# v11.net
KiCad netlist of a schematic drawn in EAGLE
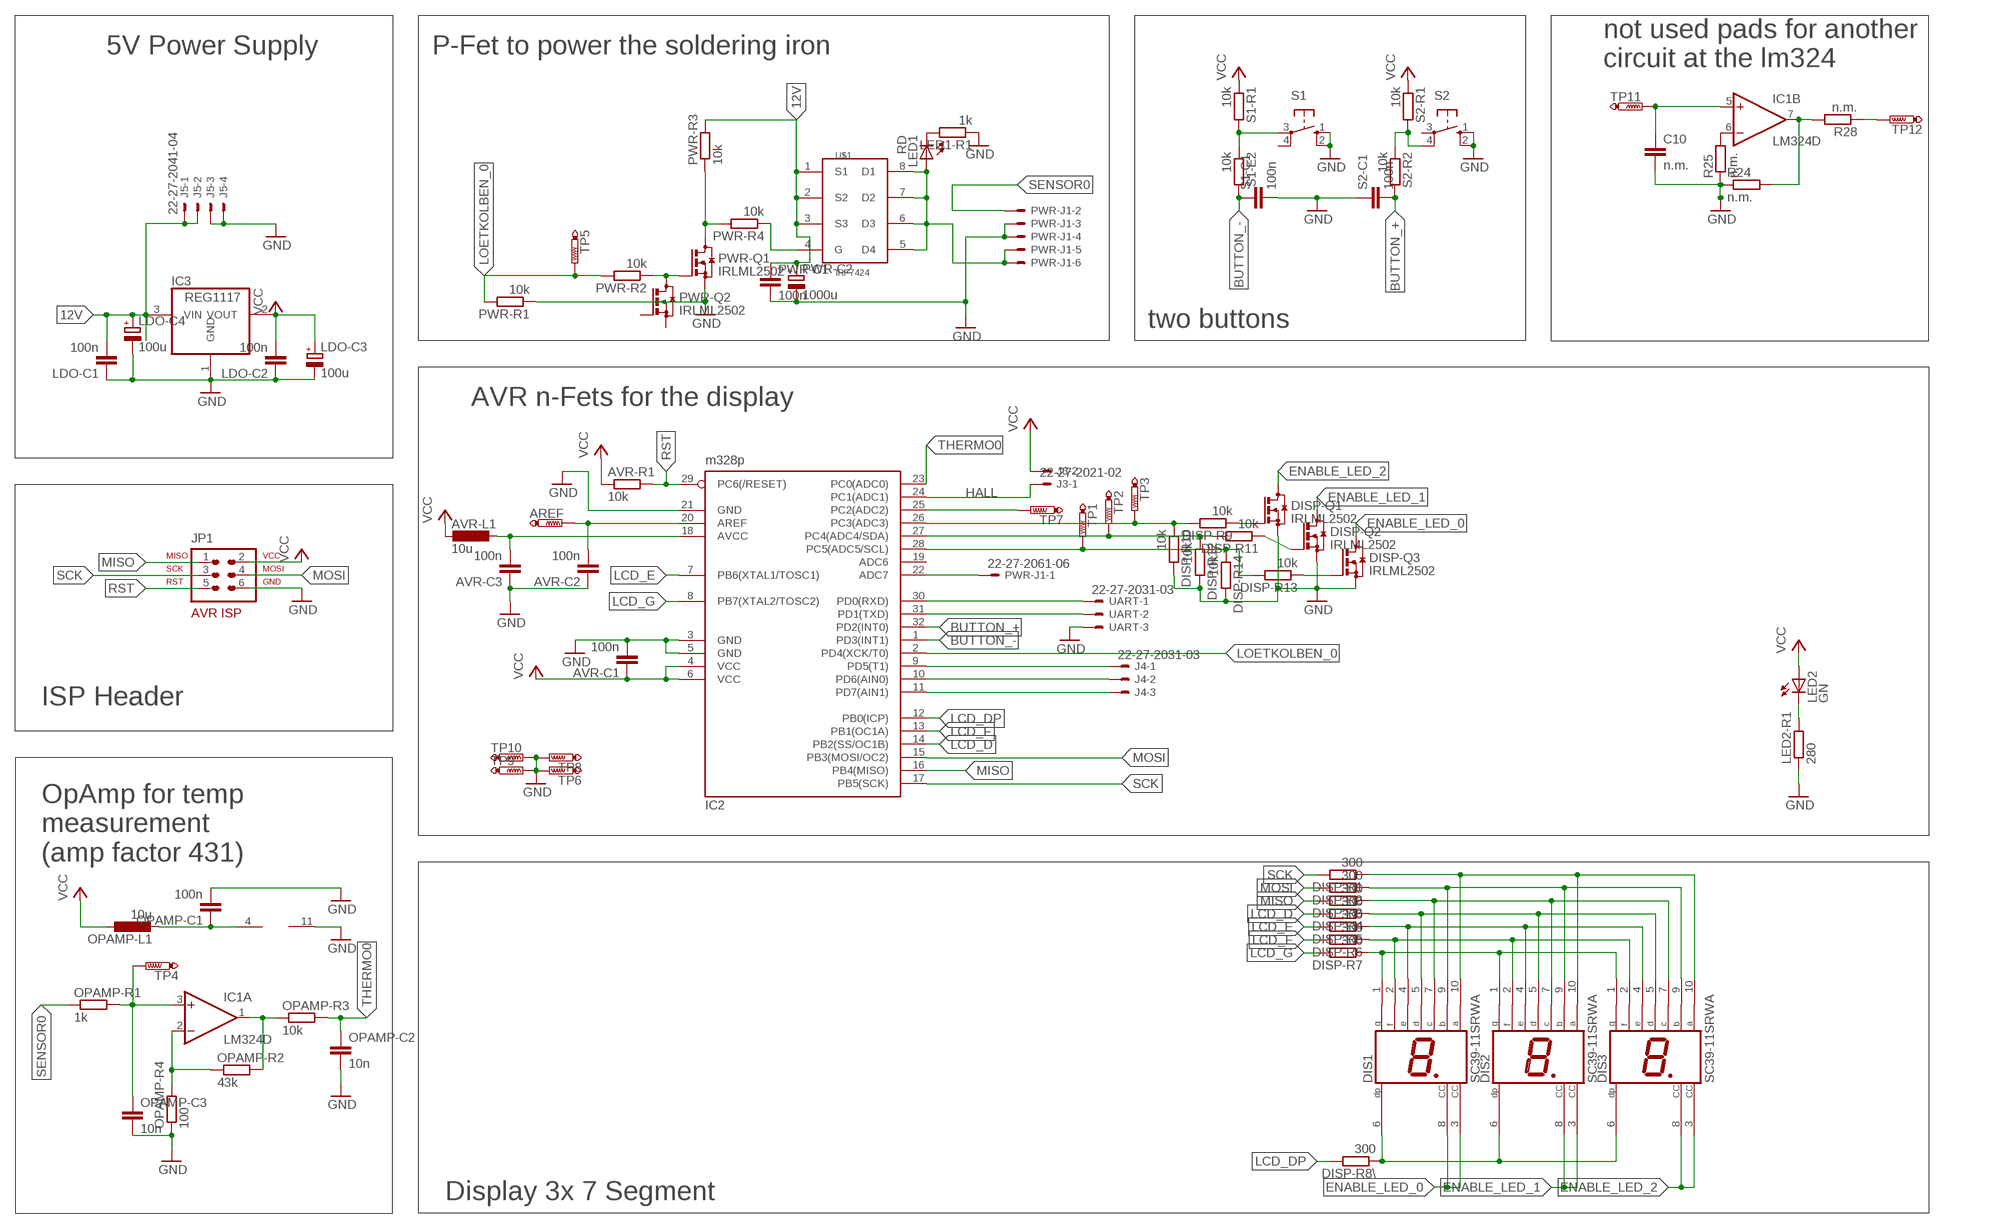
[diagram p0: schematic, sheet 1]

(export (version "E")
  (design (tool "Eeschema 10.0.6"))
  (components
    (comp (ref "AREF")
      (value "PTR1B1,27")
      (footprint "eagle-import:B1,27")
      (libsource (lib "eagle-import") (part "PTR1B1,27"))
    )
    (comp (ref "AVR-C1")
      (value "100n")
      (footprint "eagle-import:C0603")
      (libsource (lib "eagle-import") (part "C-EUC0603"))
    )
    (comp (ref "AVR-C2")
      (value "100n")
      (footprint "eagle-import:C0603")
      (libsource (lib "eagle-import") (part "C-EUC0603"))
    )
    (comp (ref "AVR-C3")
      (value "100n")
      (footprint "eagle-import:C0603")
      (libsource (lib "eagle-import") (part "C-EUC0603"))
    )
    (comp (ref "AVR-L1")
      (value "10u")
      (footprint "eagle-import:L2825P")
      (libsource (lib "eagle-import") (part "L-EUL2825P"))
    )
    (comp (ref "AVR-R1")
      (value "10k")
      (footprint "eagle-import:R0603")
      (libsource (lib "eagle-import") (part "R-EU_R0603"))
    )
    (comp (ref "C10")
      (value "n.m.")
      (footprint "eagle-import:C0603")
      (libsource (lib "eagle-import") (part "C-EUC0603"))
    )
    (comp (ref "DIS1")
      (value "SC39-11SRWA")
      (footprint "eagle-import:HDSP-E")
      (libsource (lib "eagle-import") (part "SC39-11SRWA"))
    )
    (comp (ref "DIS2")
      (value "SC39-11SRWA")
      (footprint "eagle-import:HDSP-E")
      (libsource (lib "eagle-import") (part "SC39-11SRWA"))
    )
    (comp (ref "DIS3")
      (value "SC39-11SRWA")
      (footprint "eagle-import:HDSP-E")
      (libsource (lib "eagle-import") (part "SC39-11SRWA"))
    )
    (comp (ref "DISP-Q1")
      (value "IRLML2502")
      (footprint "eagle-import:SOT23")
      (libsource (lib "eagle-import") (part "BSS123"))
    )
    (comp (ref "DISP-Q2")
      (value "IRLML2502")
      (footprint "eagle-import:SOT23")
      (libsource (lib "eagle-import") (part "BSS123"))
    )
    (comp (ref "DISP-Q3")
      (value "IRLML2502")
      (footprint "eagle-import:SOT23")
      (libsource (lib "eagle-import") (part "BSS123"))
    )
    (comp (ref "DISP-R1")
      (value "300")
      (footprint "eagle-import:R0603")
      (libsource (lib "eagle-import") (part "R-EU_R0603"))
    )
    (comp (ref "DISP-R2")
      (value "300")
      (footprint "eagle-import:R0603")
      (libsource (lib "eagle-import") (part "R-EU_R0603"))
    )
    (comp (ref "DISP-R3")
      (value "300")
      (footprint "eagle-import:R0603")
      (libsource (lib "eagle-import") (part "R-EU_R0603"))
    )
    (comp (ref "DISP-R4")
      (value "300")
      (footprint "eagle-import:R0603")
      (libsource (lib "eagle-import") (part "R-EU_R0603"))
    )
    (comp (ref "DISP-R5")
      (value "300")
      (footprint "eagle-import:R0603")
      (libsource (lib "eagle-import") (part "R-EU_R0603"))
    )
    (comp (ref "DISP-R6")
      (value "300")
      (footprint "eagle-import:R0603")
      (libsource (lib "eagle-import") (part "R-EU_R0603"))
    )
    (comp (ref "DISP-R7")
      (value "300")
      (footprint "eagle-import:R0603")
      (libsource (lib "eagle-import") (part "R-EU_R0603"))
    )
    (comp (ref "DISP-R8\\")
      (value "300")
      (footprint "eagle-import:R0603")
      (libsource (lib "eagle-import") (part "R-EU_R0603"))
    )
    (comp (ref "DISP-R9")
      (value "10k")
      (footprint "eagle-import:R0603")
      (libsource (lib "eagle-import") (part "R-EU_R0603"))
    )
    (comp (ref "DISP-R10")
      (value "10k")
      (footprint "eagle-import:R0603")
      (libsource (lib "eagle-import") (part "R-EU_R0603"))
    )
    (comp (ref "DISP-R11")
      (value "10k")
      (footprint "eagle-import:R0603")
      (libsource (lib "eagle-import") (part "R-EU_R0603"))
    )
    (comp (ref "DISP-R12")
      (value "10k")
      (footprint "eagle-import:R0603")
      (libsource (lib "eagle-import") (part "R-EU_R0603"))
    )
    (comp (ref "DISP-R13")
      (value "10k")
      (footprint "eagle-import:R0603")
      (libsource (lib "eagle-import") (part "R-EU_R0603"))
    )
    (comp (ref "DISP-R14")
      (value "10k")
      (footprint "eagle-import:R0603")
      (libsource (lib "eagle-import") (part "R-EU_R0603"))
    )
    (comp (ref "IC1")
      (value "LM324D")
      (footprint "eagle-import:SO14")
      (libsource (lib "eagle-import") (part "LM324D"))
    )
    (comp (ref "IC2")
      (value "m328p")
      (footprint "eagle-import:TQFP32-08")
      (fields (field (name "MPN") "ATMEGA8-16AU"))
      (libsource (lib "eagle-import") (part "MEGA8-AI"))
    )
    (comp (ref "IC3")
      (value "REG1117")
      (footprint "eagle-import:SOT223")
      (libsource (lib "eagle-import") (part "REG1117"))
    )
    (comp (ref "J3")
      (value "22-27-2021-02")
      (footprint "eagle-import:6410-02")
      (libsource (lib "eagle-import") (part "22-?-0227-2021"))
    )
    (comp (ref "J4")
      (value "22-27-2031-03")
      (footprint "eagle-import:6410-03")
      (libsource (lib "eagle-import") (part "22-?-0327-2031"))
    )
    (comp (ref "J5")
      (value "22-27-2041-04")
      (footprint "eagle-import:6410-04")
      (libsource (lib "eagle-import") (part "22-?-0427-2041"))
    )
    (comp (ref "JP1")
      (value "AVR-ISP-6VERT")
      (footprint "eagle-import:AVR-ISP-6")
      (libsource (lib "eagle-import") (part "AVR-ISP-6VERT"))
    )
    (comp (ref "LDO-C1")
      (value "100n")
      (footprint "eagle-import:C0603")
      (libsource (lib "eagle-import") (part "C-EUC0603"))
    )
    (comp (ref "LDO-C2")
      (value "100n")
      (footprint "eagle-import:C0603")
      (libsource (lib "eagle-import") (part "C-EUC0603"))
    )
    (comp (ref "LDO-C3")
      (value "100u")
      (footprint "eagle-import:E2-5")
      (libsource (lib "eagle-import") (part "CPOL-EUE2-5"))
    )
    (comp (ref "LDO-C4")
      (value "100u")
      (footprint "eagle-import:E2-5")
      (libsource (lib "eagle-import") (part "CPOL-EUE2-5"))
    )
    (comp (ref "LED1")
      (value "RD")
      (footprint "eagle-import:CHIP-LED0805")
      (libsource (lib "eagle-import") (part "LEDCHIP-LED0805"))
    )
    (comp (ref "LED1-R1")
      (value "1k")
      (footprint "eagle-import:R0603")
      (libsource (lib "eagle-import") (part "R-EU_R0603"))
    )
    (comp (ref "LED2")
      (value "GN")
      (footprint "eagle-import:CHIP-LED0805")
      (libsource (lib "eagle-import") (part "LEDCHIP-LED0805"))
    )
    (comp (ref "LED2-R1")
      (value "280")
      (footprint "eagle-import:R0603")
      (libsource (lib "eagle-import") (part "R-EU_R0603"))
    )
    (comp (ref "OPAMP-C1")
      (value "100n")
      (footprint "eagle-import:C0603")
      (libsource (lib "eagle-import") (part "C-EUC0603"))
    )
    (comp (ref "OPAMP-C2")
      (value "10n")
      (footprint "eagle-import:C0603")
      (libsource (lib "eagle-import") (part "C-EUC0603"))
    )
    (comp (ref "OPAMP-C3")
      (value "10n")
      (footprint "eagle-import:C0603")
      (libsource (lib "eagle-import") (part "C-EUC0603"))
    )
    (comp (ref "OPAMP-L1")
      (value "10u")
      (footprint "eagle-import:L2825P")
      (libsource (lib "eagle-import") (part "L-EUL2825P"))
    )
    (comp (ref "OPAMP-R1")
      (value "1k")
      (footprint "eagle-import:R0603")
      (libsource (lib "eagle-import") (part "R-EU_R0603"))
    )
    (comp (ref "OPAMP-R2")
      (value "43k")
      (footprint "eagle-import:R0603")
      (libsource (lib "eagle-import") (part "R-EU_R0603"))
    )
    (comp (ref "OPAMP-R3")
      (value "10k")
      (footprint "eagle-import:R0603")
      (libsource (lib "eagle-import") (part "R-EU_R0603"))
    )
    (comp (ref "OPAMP-R4")
      (value "100")
      (footprint "eagle-import:R0603")
      (libsource (lib "eagle-import") (part "R-EU_R0603"))
    )
    (comp (ref "PWR-C1")
      (value "100n")
      (footprint "eagle-import:C0603")
      (libsource (lib "eagle-import") (part "C-EUC0603"))
    )
    (comp (ref "PWR-C2")
      (value "1000u")
      (footprint "eagle-import:E5-13")
      (libsource (lib "eagle-import") (part "CPOL-EUE5-13"))
    )
    (comp (ref "PWR-J1")
      (value "22-27-2061-06")
      (footprint "eagle-import:6410-06")
      (libsource (lib "eagle-import") (part "22-?-0627-2061"))
    )
    (comp (ref "PWR-Q1")
      (value "IRLML2502")
      (footprint "eagle-import:SOT23")
      (libsource (lib "eagle-import") (part "BSS123"))
    )
    (comp (ref "PWR-Q2")
      (value "IRLML2502")
      (footprint "eagle-import:SOT23")
      (libsource (lib "eagle-import") (part "BSS123"))
    )
    (comp (ref "PWR-R1")
      (value "10k")
      (footprint "eagle-import:R0603")
      (libsource (lib "eagle-import") (part "R-EU_R0603"))
    )
    (comp (ref "PWR-R2")
      (value "10k")
      (footprint "eagle-import:R0603")
      (libsource (lib "eagle-import") (part "R-EU_R0603"))
    )
    (comp (ref "PWR-R3")
      (value "10k")
      (footprint "eagle-import:R0603")
      (libsource (lib "eagle-import") (part "R-EU_R0603"))
    )
    (comp (ref "PWR-R4")
      (value "10k")
      (footprint "eagle-import:R0603")
      (libsource (lib "eagle-import") (part "R-EU_R0603"))
    )
    (comp (ref "R24")
      (value "n.m.")
      (footprint "eagle-import:R0603")
      (libsource (lib "eagle-import") (part "R-EU_R0603"))
    )
    (comp (ref "R25")
      (value "n.m.")
      (footprint "eagle-import:R0603")
      (libsource (lib "eagle-import") (part "R-EU_R0603"))
    )
    (comp (ref "R28")
      (value "n.m.")
      (footprint "eagle-import:R0603")
      (libsource (lib "eagle-import") (part "R-EU_R0603"))
    )
    (comp (ref "S1")
      (value "10-XX")
      (footprint "eagle-import:B3F-10XX")
      (fields (field (name "MPN") "B3F-1000"))
      (libsource (lib "eagle-import") (part "10-XX"))
    )
    (comp (ref "S1-C1")
      (value "100n")
      (footprint "eagle-import:C0603")
      (libsource (lib "eagle-import") (part "C-EUC0603"))
    )
    (comp (ref "S1-E2")
      (value "10k")
      (footprint "eagle-import:R0603")
      (libsource (lib "eagle-import") (part "R-EU_R0603"))
    )
    (comp (ref "S1-R1")
      (value "10k")
      (footprint "eagle-import:R0603")
      (libsource (lib "eagle-import") (part "R-EU_R0603"))
    )
    (comp (ref "S2")
      (value "10-XX")
      (footprint "eagle-import:B3F-10XX")
      (fields (field (name "MPN") "B3F-1000"))
      (libsource (lib "eagle-import") (part "10-XX"))
    )
    (comp (ref "S2-C1")
      (value "100n")
      (footprint "eagle-import:C0603")
      (libsource (lib "eagle-import") (part "C-EUC0603"))
    )
    (comp (ref "S2-R1")
      (value "10k")
      (footprint "eagle-import:R0603")
      (libsource (lib "eagle-import") (part "R-EU_R0603"))
    )
    (comp (ref "S2-R2")
      (value "10k")
      (footprint "eagle-import:R0603")
      (libsource (lib "eagle-import") (part "R-EU_R0603"))
    )
    (comp (ref "TP1")
      (value "PTR1B1,27")
      (footprint "eagle-import:B1,27")
      (libsource (lib "eagle-import") (part "PTR1B1,27"))
    )
    (comp (ref "TP2")
      (value "PTR1B1,27")
      (footprint "eagle-import:B1,27")
      (libsource (lib "eagle-import") (part "PTR1B1,27"))
    )
    (comp (ref "TP3")
      (value "PTR1B1,27")
      (footprint "eagle-import:B1,27")
      (libsource (lib "eagle-import") (part "PTR1B1,27"))
    )
    (comp (ref "TP4")
      (value "PTR1B1,27")
      (footprint "eagle-import:B1,27")
      (libsource (lib "eagle-import") (part "PTR1B1,27"))
    )
    (comp (ref "TP5")
      (value "PTR1B1,27")
      (footprint "eagle-import:B1,27")
      (libsource (lib "eagle-import") (part "PTR1B1,27"))
    )
    (comp (ref "TP6")
      (value "PTR1B1,27")
      (footprint "eagle-import:B1,27")
      (libsource (lib "eagle-import") (part "PTR1B1,27"))
    )
    (comp (ref "TP7")
      (value "PTR1B1,27")
      (footprint "eagle-import:B1,27")
      (libsource (lib "eagle-import") (part "PTR1B1,27"))
    )
    (comp (ref "TP8")
      (value "PTR1B1,27")
      (footprint "eagle-import:B1,27")
      (libsource (lib "eagle-import") (part "PTR1B1,27"))
    )
    (comp (ref "TP9")
      (value "PTR1B1,27")
      (footprint "eagle-import:B1,27")
      (libsource (lib "eagle-import") (part "PTR1B1,27"))
    )
    (comp (ref "TP10")
      (value "PTR1B1,27")
      (footprint "eagle-import:B1,27")
      (libsource (lib "eagle-import") (part "PTR1B1,27"))
    )
    (comp (ref "TP11")
      (value "PTR1B1,27")
      (footprint "eagle-import:B1,27")
      (libsource (lib "eagle-import") (part "PTR1B1,27"))
    )
    (comp (ref "TP12")
      (value "PTR1B1,27")
      (footprint "eagle-import:B1,27")
      (libsource (lib "eagle-import") (part "PTR1B1,27"))
    )
    (comp (ref "U$1")
      (value "IRF7424")
      (footprint "eagle-import:SO-08")
      (libsource (lib "eagle-import") (part "IRF7424"))
    )
    (comp (ref "UART")
      (value "22-27-2031-03")
      (footprint "eagle-import:6410-03")
      (libsource (lib "eagle-import") (part "22-?-0327-2031"))
    )
  )
  (nets
    (net (code "1") (name "/HALL") (class "Default")
      (node (ref "IC2") (pin "24") (pinfunction "PC1(ADC1)_24") (pintype "bidirectional"))
      (node (ref "J3") (pin "1") (pinfunction "S_1") (pintype "passive"))
    )
    (net (code "2") (name "12V") (class "Default")
      (node (ref "IC3") (pin "3") (pinfunction "VIN_3") (pintype "input"))
      (node (ref "J5") (pin "1") (pinfunction "S_1") (pintype "passive"))
      (node (ref "J5") (pin "2") (pinfunction "S_2") (pintype "passive"))
      (node (ref "LDO-C1") (pin "2") (pinfunction "2_2") (pintype "passive"))
      (node (ref "LDO-C4") (pin "+") (pinfunction "+_+") (pintype "passive"))
      (node (ref "PWR-C1") (pin "1") (pinfunction "1_1") (pintype "passive"))
      (node (ref "PWR-C2") (pin "+") (pinfunction "+_+") (pintype "passive"))
      (node (ref "PWR-R3") (pin "2") (pinfunction "2_2") (pintype "passive"))
      (node (ref "U$1") (pin "1") (pinfunction "S1_1") (pintype "bidirectional"))
      (node (ref "U$1") (pin "2") (pinfunction "S2_2") (pintype "bidirectional"))
      (node (ref "U$1") (pin "3") (pinfunction "S3_3") (pintype "bidirectional"))
    )
    (net (code "3") (name "BUTTON_+") (class "Default")
      (node (ref "IC2") (pin "32") (pinfunction "PD2(INT0)_32") (pintype "bidirectional"))
      (node (ref "S2-C1") (pin "2") (pinfunction "2_2") (pintype "passive"))
      (node (ref "S2-R2") (pin "2") (pinfunction "2_2") (pintype "passive"))
    )
    (net (code "4") (name "BUTTON_-") (class "Default")
      (node (ref "IC2") (pin "1") (pinfunction "PD3(INT1)_1") (pintype "bidirectional"))
      (node (ref "S1-C1") (pin "1") (pinfunction "1_1") (pintype "passive"))
      (node (ref "S1-E2") (pin "2") (pinfunction "2_2") (pintype "passive"))
    )
    (net (code "5") (name "ENABLE_LED_0") (class "Default")
      (node (ref "DIS1") (pin "3") (pinfunction "CC_3") (pintype "passive"))
      (node (ref "DIS1") (pin "8") (pinfunction "CC_8") (pintype "passive"))
      (node (ref "DISP-Q3") (pin "3") (pinfunction "D_3") (pintype "passive"))
    )
    (net (code "6") (name "ENABLE_LED_1") (class "Default")
      (node (ref "DIS2") (pin "3") (pinfunction "CC_3") (pintype "passive"))
      (node (ref "DIS2") (pin "8") (pinfunction "CC_8") (pintype "passive"))
      (node (ref "DISP-Q2") (pin "3") (pinfunction "D_3") (pintype "passive"))
    )
    (net (code "7") (name "ENABLE_LED_2") (class "Default")
      (node (ref "DIS3") (pin "3") (pinfunction "CC_3") (pintype "passive"))
      (node (ref "DIS3") (pin "8") (pinfunction "CC_8") (pintype "passive"))
      (node (ref "DISP-Q1") (pin "3") (pinfunction "D_3") (pintype "passive"))
    )
    (net (code "8") (name "GND") (class "Default")
      (node (ref "AVR-C1") (pin "2") (pinfunction "2_2") (pintype "passive"))
      (node (ref "AVR-C2") (pin "1") (pinfunction "1_1") (pintype "passive"))
      (node (ref "AVR-C3") (pin "1") (pinfunction "1_1") (pintype "passive"))
      (node (ref "C10") (pin "2") (pinfunction "2_2") (pintype "passive"))
      (node (ref "DISP-Q1") (pin "2") (pinfunction "S_2") (pintype "passive"))
      (node (ref "DISP-Q2") (pin "2") (pinfunction "S_2") (pintype "passive"))
      (node (ref "DISP-Q3") (pin "2") (pinfunction "S_2") (pintype "passive"))
      (node (ref "DISP-R10") (pin "2") (pinfunction "2_2") (pintype "passive"))
      (node (ref "DISP-R12") (pin "2") (pinfunction "2_2") (pintype "passive"))
      (node (ref "DISP-R14") (pin "2") (pinfunction "2_2") (pintype "passive"))
      (node (ref "IC1") (pin "11") (pinfunction "V-_11") (pintype "power_in"))
      (node (ref "IC2") (pin "21") (pinfunction "GND_21") (pintype "power_in"))
      (node (ref "IC2") (pin "3") (pinfunction "GND_3") (pintype "power_in"))
      (node (ref "IC2") (pin "5") (pinfunction "GND_5") (pintype "power_in"))
      (node (ref "IC3") (pin "1") (pinfunction "GND_1") (pintype "power_in"))
      (node (ref "J5") (pin "3") (pinfunction "S_3") (pintype "passive"))
      (node (ref "J5") (pin "4") (pinfunction "S_4") (pintype "passive"))
      (node (ref "JP1") (pin "6") (pinfunction "6_6") (pintype "passive"))
      (node (ref "LDO-C1") (pin "1") (pinfunction "1_1") (pintype "passive"))
      (node (ref "LDO-C2") (pin "1") (pinfunction "1_1") (pintype "passive"))
      (node (ref "LDO-C3") (pin "-") (pinfunction "-_-") (pintype "passive"))
      (node (ref "LDO-C4") (pin "-") (pinfunction "-_-") (pintype "passive"))
      (node (ref "LED1-R1") (pin "1") (pinfunction "1_1") (pintype "passive"))
      (node (ref "LED2-R1") (pin "1") (pinfunction "1_1") (pintype "passive"))
      (node (ref "OPAMP-C1") (pin "2") (pinfunction "2_2") (pintype "passive"))
      (node (ref "OPAMP-C2") (pin "2") (pinfunction "2_2") (pintype "passive"))
      (node (ref "OPAMP-C3") (pin "2") (pinfunction "2_2") (pintype "passive"))
      (node (ref "OPAMP-R4") (pin "1") (pinfunction "1_1") (pintype "passive"))
      (node (ref "PWR-C1") (pin "2") (pinfunction "2_2") (pintype "passive"))
      (node (ref "PWR-C2") (pin "-") (pinfunction "-_-") (pintype "passive"))
      (node (ref "PWR-J1") (pin "3") (pinfunction "S_3") (pintype "passive"))
      (node (ref "PWR-J1") (pin "4") (pinfunction "S_4") (pintype "passive"))
      (node (ref "PWR-Q1") (pin "2") (pinfunction "S_2") (pintype "passive"))
      (node (ref "PWR-R1") (pin "1") (pinfunction "1_1") (pintype "passive"))
      (node (ref "R24") (pin "1") (pinfunction "1_1") (pintype "passive"))
      (node (ref "R25") (pin "1") (pinfunction "1_1") (pintype "passive"))
      (node (ref "S1") (pin "1") (pinfunction "S_1") (pintype "passive"))
      (node (ref "S1") (pin "2") (pinfunction "S1_2") (pintype "passive"))
      (node (ref "S1-C1") (pin "2") (pinfunction "2_2") (pintype "passive"))
      (node (ref "S2") (pin "1") (pinfunction "S_1") (pintype "passive"))
      (node (ref "S2") (pin "2") (pinfunction "S1_2") (pintype "passive"))
      (node (ref "S2-C1") (pin "1") (pinfunction "1_1") (pintype "passive"))
      (node (ref "TP10") (pin "TP") (pinfunction "TP_TP") (pintype "input"))
      (node (ref "TP6") (pin "TP") (pinfunction "TP_TP") (pintype "input"))
      (node (ref "TP8") (pin "TP") (pinfunction "TP_TP") (pintype "input"))
      (node (ref "TP9") (pin "TP") (pinfunction "TP_TP") (pintype "input"))
      (node (ref "UART") (pin "3") (pinfunction "S_3") (pintype "passive"))
    )
    (net (code "9") (name "LCD_D") (class "Default")
      (node (ref "DISP-R4") (pin "2") (pinfunction "2_2") (pintype "passive"))
      (node (ref "IC2") (pin "14") (pinfunction "PB2(SS/OC1B)_14") (pintype "bidirectional"))
    )
    (net (code "10") (name "LCD_DP") (class "Default")
      (node (ref "DISP-R8\\") (pin "2") (pinfunction "2_2") (pintype "passive"))
      (node (ref "IC2") (pin "12") (pinfunction "PB0(ICP)_12") (pintype "bidirectional"))
    )
    (net (code "11") (name "LCD_E") (class "Default")
      (node (ref "DISP-R5") (pin "2") (pinfunction "2_2") (pintype "passive"))
      (node (ref "IC2") (pin "7") (pinfunction "PB6(XTAL1/TOSC1)_7") (pintype "bidirectional"))
    )
    (net (code "12") (name "LCD_F") (class "Default")
      (node (ref "DISP-R6") (pin "2") (pinfunction "2_2") (pintype "passive"))
      (node (ref "IC2") (pin "13") (pinfunction "PB1(OC1A)_13") (pintype "bidirectional"))
    )
    (net (code "13") (name "LCD_G") (class "Default")
      (node (ref "DISP-R7") (pin "2") (pinfunction "2_2") (pintype "passive"))
      (node (ref "IC2") (pin "8") (pinfunction "PB7(XTAL2/TOSC2)_8") (pintype "bidirectional"))
    )
    (net (code "14") (name "LOETKOLBEN_0") (class "Default")
      (node (ref "IC2") (pin "2") (pinfunction "PD4(XCK/T0)_2") (pintype "bidirectional"))
      (node (ref "PWR-R1") (pin "2") (pinfunction "2_2") (pintype "passive"))
      (node (ref "PWR-R2") (pin "2") (pinfunction "2_2") (pintype "passive"))
      (node (ref "TP5") (pin "TP") (pinfunction "TP_TP") (pintype "input"))
    )
    (net (code "15") (name "MISO") (class "Default")
      (node (ref "DISP-R3") (pin "2") (pinfunction "2_2") (pintype "passive"))
      (node (ref "IC2") (pin "16") (pinfunction "PB4(MISO)_16") (pintype "bidirectional"))
      (node (ref "JP1") (pin "1") (pinfunction "1_1") (pintype "passive"))
    )
    (net (code "16") (name "MOSI") (class "Default")
      (node (ref "DISP-R2") (pin "2") (pinfunction "2_2") (pintype "passive"))
      (node (ref "IC2") (pin "15") (pinfunction "PB3(MOSI/OC2)_15") (pintype "bidirectional"))
      (node (ref "JP1") (pin "4") (pinfunction "4_4") (pintype "passive"))
    )
    (net (code "17") (name "Net-(DIS1-A)") (class "Default")
      (node (ref "DIS1") (pin "10") (pinfunction "A_10") (pintype "passive"))
      (node (ref "DIS2") (pin "10") (pinfunction "A_10") (pintype "passive"))
      (node (ref "DIS3") (pin "10") (pinfunction "A_10") (pintype "passive"))
      (node (ref "DISP-R1") (pin "1") (pinfunction "1_1") (pintype "passive"))
    )
    (net (code "18") (name "Net-(DIS1-B)") (class "Default")
      (node (ref "DIS1") (pin "9") (pinfunction "B_9") (pintype "passive"))
      (node (ref "DIS2") (pin "9") (pinfunction "B_9") (pintype "passive"))
      (node (ref "DIS3") (pin "9") (pinfunction "B_9") (pintype "passive"))
      (node (ref "DISP-R2") (pin "1") (pinfunction "1_1") (pintype "passive"))
    )
    (net (code "19") (name "Net-(DIS1-C)") (class "Default")
      (node (ref "DIS1") (pin "7") (pinfunction "C_7") (pintype "passive"))
      (node (ref "DIS2") (pin "7") (pinfunction "C_7") (pintype "passive"))
      (node (ref "DIS3") (pin "7") (pinfunction "C_7") (pintype "passive"))
      (node (ref "DISP-R3") (pin "1") (pinfunction "1_1") (pintype "passive"))
    )
    (net (code "20") (name "Net-(DIS1-D)") (class "Default")
      (node (ref "DIS1") (pin "5") (pinfunction "D_5") (pintype "passive"))
      (node (ref "DIS2") (pin "5") (pinfunction "D_5") (pintype "passive"))
      (node (ref "DIS3") (pin "5") (pinfunction "D_5") (pintype "passive"))
      (node (ref "DISP-R4") (pin "1") (pinfunction "1_1") (pintype "passive"))
    )
    (net (code "21") (name "Net-(DIS1-DP)") (class "Default")
      (node (ref "DIS1") (pin "6") (pinfunction "DP_6") (pintype "passive"))
      (node (ref "DIS2") (pin "6") (pinfunction "DP_6") (pintype "passive"))
      (node (ref "DIS3") (pin "6") (pinfunction "DP_6") (pintype "passive"))
      (node (ref "DISP-R8\\") (pin "1") (pinfunction "1_1") (pintype "passive"))
    )
    (net (code "22") (name "Net-(DIS1-E)") (class "Default")
      (node (ref "DIS1") (pin "4") (pinfunction "E_4") (pintype "passive"))
      (node (ref "DIS2") (pin "4") (pinfunction "E_4") (pintype "passive"))
      (node (ref "DIS3") (pin "4") (pinfunction "E_4") (pintype "passive"))
      (node (ref "DISP-R5") (pin "1") (pinfunction "1_1") (pintype "passive"))
    )
    (net (code "23") (name "Net-(DIS1-F)") (class "Default")
      (node (ref "DIS1") (pin "2") (pinfunction "F_2") (pintype "passive"))
      (node (ref "DIS2") (pin "2") (pinfunction "F_2") (pintype "passive"))
      (node (ref "DIS3") (pin "2") (pinfunction "F_2") (pintype "passive"))
      (node (ref "DISP-R6") (pin "1") (pinfunction "1_1") (pintype "passive"))
    )
    (net (code "24") (name "Net-(DIS1-G)") (class "Default")
      (node (ref "DIS1") (pin "1") (pinfunction "G_1") (pintype "passive"))
      (node (ref "DIS2") (pin "1") (pinfunction "G_1") (pintype "passive"))
      (node (ref "DIS3") (pin "1") (pinfunction "G_1") (pintype "passive"))
      (node (ref "DISP-R7") (pin "1") (pinfunction "1_1") (pintype "passive"))
    )
    (net (code "25") (name "Net-(DISP-Q1-G)") (class "Default")
      (node (ref "DISP-Q1") (pin "1") (pinfunction "G_1") (pintype "passive"))
      (node (ref "DISP-R9") (pin "1") (pinfunction "1_1") (pintype "passive"))
    )
    (net (code "26") (name "Net-(DISP-Q2-G)") (class "Default")
      (node (ref "DISP-Q2") (pin "1") (pinfunction "G_1") (pintype "passive"))
      (node (ref "DISP-R11") (pin "1") (pinfunction "1_1") (pintype "passive"))
    )
    (net (code "27") (name "Net-(DISP-Q3-G)") (class "Default")
      (node (ref "DISP-Q3") (pin "1") (pinfunction "G_1") (pintype "passive"))
      (node (ref "DISP-R13") (pin "1") (pinfunction "1_1") (pintype "passive"))
    )
    (net (code "28") (name "Net-(IC1A-+IN)") (class "Default")
      (node (ref "IC1") (pin "3") (pinfunction "+IN_3") (pintype "input"))
      (node (ref "OPAMP-C3") (pin "1") (pinfunction "1_1") (pintype "passive"))
      (node (ref "OPAMP-R1") (pin "2") (pinfunction "2_2") (pintype "passive"))
      (node (ref "TP4") (pin "TP") (pinfunction "TP_TP") (pintype "input"))
    )
    (net (code "29") (name "Net-(IC1A--IN)") (class "Default")
      (node (ref "IC1") (pin "2") (pinfunction "-IN_2") (pintype "input"))
      (node (ref "OPAMP-R2") (pin "1") (pinfunction "1_1") (pintype "passive"))
      (node (ref "OPAMP-R4") (pin "2") (pinfunction "2_2") (pintype "passive"))
    )
    (net (code "30") (name "Net-(IC1A-OUT)") (class "Default")
      (node (ref "IC1") (pin "1") (pinfunction "OUT_1") (pintype "output"))
      (node (ref "OPAMP-R2") (pin "2") (pinfunction "2_2") (pintype "passive"))
      (node (ref "OPAMP-R3") (pin "1") (pinfunction "1_1") (pintype "passive"))
    )
    (net (code "31") (name "Net-(IC1B-+IN)") (class "Default")
      (node (ref "C10") (pin "1") (pinfunction "1_1") (pintype "passive"))
      (node (ref "IC1") (pin "5") (pinfunction "+IN_5") (pintype "input"))
      (node (ref "TP11") (pin "TP") (pinfunction "TP_TP") (pintype "input"))
    )
    (net (code "32") (name "Net-(IC1B--IN)") (class "Default")
      (node (ref "IC1") (pin "6") (pinfunction "-IN_6") (pintype "input"))
      (node (ref "R25") (pin "2") (pinfunction "2_2") (pintype "passive"))
    )
    (net (code "33") (name "Net-(IC1B-OUT)") (class "Default")
      (node (ref "IC1") (pin "7") (pinfunction "OUT_7") (pintype "output"))
      (node (ref "R24") (pin "2") (pinfunction "2_2") (pintype "passive"))
      (node (ref "R28") (pin "2") (pinfunction "2_2") (pintype "passive"))
    )
    (net (code "34") (name "Net-(IC1E-V+)") (class "Default")
      (node (ref "IC1") (pin "4") (pinfunction "V+_4") (pintype "power_in"))
      (node (ref "OPAMP-C1") (pin "1") (pinfunction "1_1") (pintype "passive"))
      (node (ref "OPAMP-L1") (pin "2") (pinfunction "2_2") (pintype "passive"))
    )
    (net (code "35") (name "Net-(IC2-ADC7)") (class "Default")
      (node (ref "IC2") (pin "22") (pinfunction "ADC7_22") (pintype "bidirectional"))
      (node (ref "PWR-J1") (pin "1") (pinfunction "S_1") (pintype "passive"))
    )
    (net (code "36") (name "Net-(IC2-AREF)") (class "Default")
      (node (ref "AREF") (pin "TP") (pinfunction "TP_TP") (pintype "input"))
      (node (ref "AVR-C2") (pin "2") (pinfunction "2_2") (pintype "passive"))
      (node (ref "IC2") (pin "20") (pinfunction "AREF_20") (pintype "passive"))
    )
    (net (code "37") (name "Net-(IC2-AVCC)") (class "Default")
      (node (ref "AVR-C3") (pin "2") (pinfunction "2_2") (pintype "passive"))
      (node (ref "AVR-L1") (pin "1") (pinfunction "1_1") (pintype "passive"))
      (node (ref "IC2") (pin "18") (pinfunction "AVCC_18") (pintype "power_in"))
    )
    (net (code "38") (name "Net-(IC2-PC2(ADC2))") (class "Default")
      (node (ref "IC2") (pin "25") (pinfunction "PC2(ADC2)_25") (pintype "bidirectional"))
      (node (ref "TP7") (pin "TP") (pinfunction "TP_TP") (pintype "input"))
    )
    (net (code "39") (name "Net-(IC2-PC3(ADC3))") (class "Default")
      (node (ref "DISP-R10") (pin "1") (pinfunction "1_1") (pintype "passive"))
      (node (ref "DISP-R9") (pin "2") (pinfunction "2_2") (pintype "passive"))
      (node (ref "IC2") (pin "26") (pinfunction "PC3(ADC3)_26") (pintype "bidirectional"))
      (node (ref "TP3") (pin "TP") (pinfunction "TP_TP") (pintype "input"))
    )
    (net (code "40") (name "Net-(IC2-PC4(ADC4{slash}SDA))") (class "Default")
      (node (ref "DISP-R11") (pin "2") (pinfunction "2_2") (pintype "passive"))
      (node (ref "DISP-R12") (pin "1") (pinfunction "1_1") (pintype "passive"))
      (node (ref "IC2") (pin "27") (pinfunction "PC4(ADC4/SDA)_27") (pintype "bidirectional"))
      (node (ref "TP2") (pin "TP") (pinfunction "TP_TP") (pintype "input"))
    )
    (net (code "41") (name "Net-(IC2-PC5(ADC5{slash}SCL))") (class "Default")
      (node (ref "DISP-R13") (pin "2") (pinfunction "2_2") (pintype "passive"))
      (node (ref "DISP-R14") (pin "1") (pinfunction "1_1") (pintype "passive"))
      (node (ref "IC2") (pin "28") (pinfunction "PC5(ADC5/SCL)_28") (pintype "bidirectional"))
      (node (ref "TP1") (pin "TP") (pinfunction "TP_TP") (pintype "input"))
    )
    (net (code "42") (name "Net-(IC2-PD0(RXD))") (class "Default")
      (node (ref "IC2") (pin "30") (pinfunction "PD0(RXD)_30") (pintype "bidirectional"))
      (node (ref "UART") (pin "1") (pinfunction "S_1") (pintype "passive"))
    )
    (net (code "43") (name "Net-(IC2-PD1(TXD))") (class "Default")
      (node (ref "IC2") (pin "31") (pinfunction "PD1(TXD)_31") (pintype "bidirectional"))
      (node (ref "UART") (pin "2") (pinfunction "S_2") (pintype "passive"))
    )
    (net (code "44") (name "Net-(IC2-PD5(T1))") (class "Default")
      (node (ref "IC2") (pin "9") (pinfunction "PD5(T1)_9") (pintype "bidirectional"))
      (node (ref "J4") (pin "1") (pinfunction "S_1") (pintype "passive"))
    )
    (net (code "45") (name "Net-(IC2-PD6(AIN0))") (class "Default")
      (node (ref "IC2") (pin "10") (pinfunction "PD6(AIN0)_10") (pintype "bidirectional"))
      (node (ref "J4") (pin "2") (pinfunction "S_2") (pintype "passive"))
    )
    (net (code "46") (name "Net-(IC2-PD7(AIN1))") (class "Default")
      (node (ref "IC2") (pin "11") (pinfunction "PD7(AIN1)_11") (pintype "bidirectional"))
      (node (ref "J4") (pin "3") (pinfunction "S_3") (pintype "passive"))
    )
    (net (code "47") (name "Net-(LED1-PadC)") (class "Default")
      (node (ref "LED1") (pin "C") (pinfunction "C_C") (pintype "passive"))
      (node (ref "LED1-R1") (pin "2") (pinfunction "2_2") (pintype "passive"))
    )
    (net (code "48") (name "Net-(LED2-PadC)") (class "Default")
      (node (ref "LED2") (pin "C") (pinfunction "C_C") (pintype "passive"))
      (node (ref "LED2-R1") (pin "2") (pinfunction "2_2") (pintype "passive"))
    )
    (net (code "49") (name "Net-(PWR-J1E-S)") (class "Default")
      (node (ref "LED1") (pin "A") (pinfunction "A_A") (pintype "passive"))
      (node (ref "PWR-J1") (pin "5") (pinfunction "S_5") (pintype "passive"))
      (node (ref "PWR-J1") (pin "6") (pinfunction "S_6") (pintype "passive"))
      (node (ref "U$1") (pin "5") (pinfunction "D4_5") (pintype "bidirectional"))
      (node (ref "U$1") (pin "6") (pinfunction "D3_6") (pintype "bidirectional"))
      (node (ref "U$1") (pin "7") (pinfunction "D2_7") (pintype "bidirectional"))
      (node (ref "U$1") (pin "8") (pinfunction "D1_8") (pintype "bidirectional"))
    )
    (net (code "50") (name "Net-(PWR-Q1-D)") (class "Default")
      (node (ref "PWR-Q1") (pin "3") (pinfunction "D_3") (pintype "passive"))
      (node (ref "PWR-R3") (pin "1") (pinfunction "1_1") (pintype "passive"))
      (node (ref "PWR-R4") (pin "2") (pinfunction "2_2") (pintype "passive"))
    )
    (net (code "51") (name "Net-(PWR-Q1-G)") (class "Default")
      (node (ref "PWR-Q1") (pin "1") (pinfunction "G_1") (pintype "passive"))
      (node (ref "PWR-Q2") (pin "3") (pinfunction "D_3") (pintype "passive"))
      (node (ref "PWR-R2") (pin "1") (pinfunction "1_1") (pintype "passive"))
    )
    (net (code "52") (name "Net-(R28-Pad1)") (class "Default")
      (node (ref "R28") (pin "1") (pinfunction "1_1") (pintype "passive"))
      (node (ref "TP12") (pin "TP") (pinfunction "TP_TP") (pintype "input"))
    )
    (net (code "53") (name "Net-(S1-P)") (class "Default")
      (node (ref "S1") (pin "3") (pinfunction "P_3") (pintype "passive"))
      (node (ref "S1-E2") (pin "1") (pinfunction "1_1") (pintype "passive"))
      (node (ref "S1-R1") (pin "2") (pinfunction "2_2") (pintype "passive"))
    )
    (net (code "54") (name "Net-(S2-P1)") (class "Default")
      (node (ref "S2") (pin "4") (pinfunction "P1_4") (pintype "passive"))
      (node (ref "S2-R1") (pin "2") (pinfunction "2_2") (pintype "passive"))
      (node (ref "S2-R2") (pin "1") (pinfunction "1_1") (pintype "passive"))
    )
    (net (code "55") (name "Net-(U$1-G)") (class "Default")
      (node (ref "PWR-R4") (pin "1") (pinfunction "1_1") (pintype "passive"))
      (node (ref "U$1") (pin "4") (pinfunction "G_4") (pintype "bidirectional"))
    )
    (net (code "56") (name "RST") (class "Default")
      (node (ref "AVR-R1") (pin "2") (pinfunction "2_2") (pintype "passive"))
      (node (ref "IC2") (pin "29") (pinfunction "PC6(/RESET)_29") (pintype "bidirectional"))
      (node (ref "JP1") (pin "5") (pinfunction "5_5") (pintype "passive"))
    )
    (net (code "57") (name "SCK") (class "Default")
      (node (ref "DISP-R1") (pin "2") (pinfunction "2_2") (pintype "passive"))
      (node (ref "IC2") (pin "17") (pinfunction "PB5(SCK)_17") (pintype "bidirectional"))
      (node (ref "JP1") (pin "3") (pinfunction "3_3") (pintype "passive"))
    )
    (net (code "58") (name "SENSOR0") (class "Default")
      (node (ref "OPAMP-R1") (pin "1") (pinfunction "1_1") (pintype "passive"))
      (node (ref "PWR-J1") (pin "2") (pinfunction "S_2") (pintype "passive"))
    )
    (net (code "59") (name "THERMO0") (class "Default")
      (node (ref "IC2") (pin "23") (pinfunction "PC0(ADC0)_23") (pintype "bidirectional"))
      (node (ref "OPAMP-C2") (pin "1") (pinfunction "1_1") (pintype "passive"))
      (node (ref "OPAMP-R3") (pin "2") (pinfunction "2_2") (pintype "passive"))
    )
    (net (code "60") (name "VCC") (class "Default")
      (node (ref "AVR-C1") (pin "1") (pinfunction "1_1") (pintype "passive"))
      (node (ref "AVR-L1") (pin "2") (pinfunction "2_2") (pintype "passive"))
      (node (ref "AVR-R1") (pin "1") (pinfunction "1_1") (pintype "passive"))
      (node (ref "IC2") (pin "4") (pinfunction "VCC_4") (pintype "power_in"))
      (node (ref "IC2") (pin "6") (pinfunction "VCC_6") (pintype "power_in"))
      (node (ref "IC3") (pin "2") (pinfunction "VOUT_2") (pintype "output"))
      (node (ref "J3") (pin "2") (pinfunction "S_2") (pintype "passive"))
      (node (ref "JP1") (pin "2") (pinfunction "2_2") (pintype "passive"))
      (node (ref "LDO-C2") (pin "2") (pinfunction "2_2") (pintype "passive"))
      (node (ref "LDO-C3") (pin "+") (pinfunction "+_+") (pintype "passive"))
      (node (ref "LED2") (pin "A") (pinfunction "A_A") (pintype "passive"))
      (node (ref "OPAMP-L1") (pin "1") (pinfunction "1_1") (pintype "passive"))
      (node (ref "S1-R1") (pin "1") (pinfunction "1_1") (pintype "passive"))
      (node (ref "S2-R1") (pin "1") (pinfunction "1_1") (pintype "passive"))
    )
    (net (code "61") (name "unconnected-(IC2-ADC6-Pad19)") (class "Default")
      (node (ref "IC2") (pin "19") (pinfunction "ADC6_19") (pintype "bidirectional"))
    )
    (net (code "62") (name "unconnected-(PWR-Q2-G-Pad1)") (class "Default")
      (node (ref "PWR-Q2") (pin "1") (pinfunction "G_1") (pintype "passive"))
    )
    (net (code "63") (name "unconnected-(PWR-Q2-S-Pad2)") (class "Default")
      (node (ref "PWR-Q2") (pin "2") (pinfunction "S_2") (pintype "passive"))
    )
    (net (code "64") (name "unconnected-(S1-P1-Pad4)") (class "Default")
      (node (ref "S1") (pin "4") (pinfunction "P1_4") (pintype "passive"))
    )
    (net (code "65") (name "unconnected-(S2-P-Pad3)") (class "Default")
      (node (ref "S2") (pin "3") (pinfunction "P_3") (pintype "passive"))
    )
  )
)
